# 5V_Power_Supply.net
KiCad netlist of a schematic drawn in Altium Designer
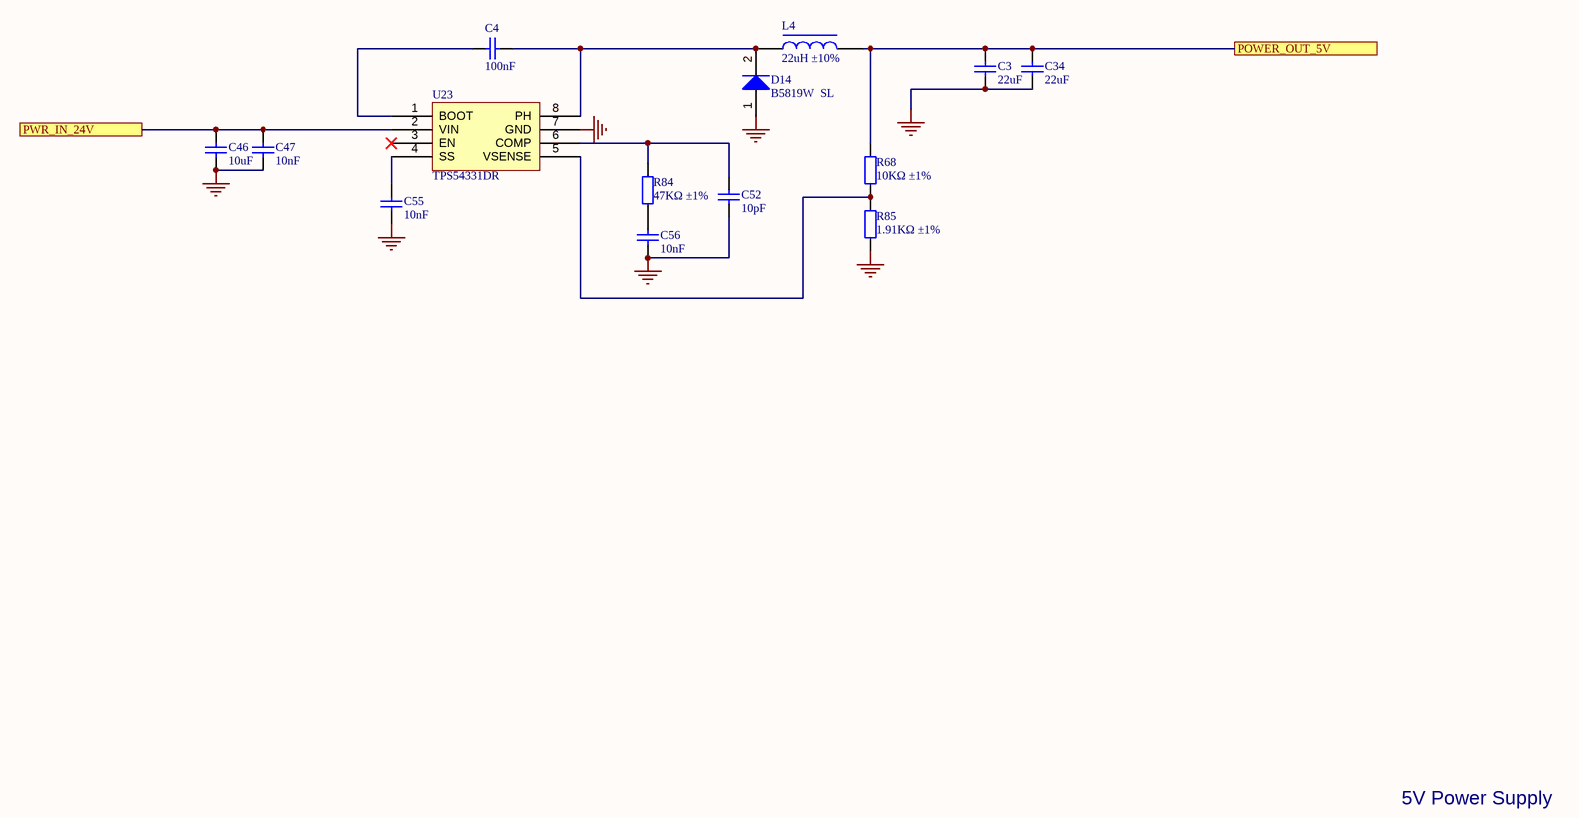
[diagram p0: 5V_Power_Supply.SchDoc]

(export (version "E")
  (design (tool "Eeschema 10.0.6"))
  (components
    (comp (ref "C3")
      (value "22uF")
      (footprint "0805_C")
      (description "Chip capacitors")
      (fields
        (field (name "MANUFACTURER") "Samsung Electro-Mechanics")
        (field (name "PARTNUMBER") "CL21A226MAQNNNE")
      )
      (libsource (lib "Cap") (part "0805 22uF (226) 20% 25V"))
    )
    (comp (ref "C4")
      (value "100nF")
      (footprint "0402_C")
      (description "Chip capacitors")
      (fields
        (field (name "MANUFACTURER") "Samsung Electro-Mechanics")
        (field (name "PARTNUMBER") "CL05B104KO5NNNC")
      )
      (libsource (lib "Cap") (part "0402 100nF (104) 10% 16V"))
    )
    (comp (ref "C34")
      (value "22uF")
      (footprint "0805_C")
      (description "Chip capacitors")
      (fields
        (field (name "MANUFACTURER") "Samsung Electro-Mechanics")
        (field (name "PARTNUMBER") "CL21A226MAQNNNE")
      )
      (libsource (lib "Cap") (part "0805 22uF (226) 20% 25V"))
    )
    (comp (ref "C46")
      (value "10uF")
      (footprint "1206_C")
      (description "Chip capacitors")
      (fields
        (field (name "MANUFACTURER") "Samsung Electro-Mechanics")
        (field (name "PARTNUMBER") "CL31A106KBHNNNE")
      )
      (libsource (lib "Cap") (part "1206 10uF (106) 10% 50V"))
    )
    (comp (ref "C47")
      (value "10nF")
      (footprint "0402_C")
      (description "Chip capacitors")
      (fields
        (field (name "MANUFACTURER") "Samsung Electro-Mechanics")
        (field (name "PARTNUMBER") "CL05B103KB5NNNC")
      )
      (libsource (lib "Cap") (part "0402 10nF (103) 10% 50V"))
    )
    (comp (ref "C52")
      (value "10pF")
      (footprint "0402_C")
      (description "Chip capacitors")
      (fields
        (field (name "MANUFACTURER") "Samsung Electro-Mechanics")
        (field (name "PARTNUMBER") "CL05C100JB5NNNC")
      )
      (libsource (lib "Cap") (part "0402 10pF (100) 5% 50V"))
    )
    (comp (ref "C55")
      (value "10nF")
      (footprint "0402_C")
      (description "Chip capacitors")
      (fields
        (field (name "MANUFACTURER") "Samsung Electro-Mechanics")
        (field (name "PARTNUMBER") "CL05B103KB5NNNC")
      )
      (libsource (lib "Cap") (part "0402 10nF (103) 10% 50V"))
    )
    (comp (ref "C56")
      (value "10nF")
      (footprint "0402_C")
      (description "Chip capacitors")
      (fields
        (field (name "MANUFACTURER") "Samsung Electro-Mechanics")
        (field (name "PARTNUMBER") "CL05B103KB5NNNC")
      )
      (libsource (lib "Cap") (part "0402 10nF (103) 10% 50V"))
    )
    (comp (ref "D14")
      (value "B5819W  SL")
      (footprint "SOD-123")
      (description "Schottky Diode")
      (libsource (lib "Diode") (part "SOD-123 B5819W  SL"))
    )
    (comp (ref "L4")
      (value "22uH ±10%")
      (footprint "INDP4040X30N")
      (description "1A 22uH ±20% SMD,4x4x3mm Power Inductors ROHS")
      (libsource (lib "IUD") (part "4x4x3 22uH 20%"))
    )
    (comp (ref "R68")
      (value "10KΩ ±1%")
      (footprint "0603_R")
      (description "Chip resistor")
      (fields (field (name "MANUFACTURER") "Uniroyal Elec") (field (name "PARTNUMBER") "0603WAF1002T5E"))
      (libsource (lib "RES") (part "0603 10K (1002) 1%"))
    )
    (comp (ref "R84")
      (value "47KΩ ±1%")
      (footprint "0402_R")
      (description "Chip resistor")
      (fields (field (name "MANUFACTURER") "Uniroyal Elec") (field (name "PARTNUMBER") "0402WGF4702TCE"))
      (libsource (lib "RES") (part "0402 47K (4702) 1%"))
    )
    (comp (ref "R85")
      (value "1.91KΩ ±1%")
      (footprint "0603_R")
      (description "Chip resistor")
      (fields (field (name "MANUFACTURER") "Uniroyal Elec") (field (name "PARTNUMBER") "0603WAF1911T5E"))
      (libsource (lib "RES") (part "0603 2K (2001) 1%"))
    )
    (comp (ref "U23")
      (value "TPS54331DR")
      (footprint "Miscellaneous Devices LC:SOIC-8_150mil")
      (description "Switching Voltage Regulators 3A 28V In Step Down SWIFT DC/DC Cnvrtr")
      (libsource (lib "PrintNC_GRBLHAL_Breakout") (part "TPS54331DR_[C9865]"))
    )
  )
  (nets
    (net (code "1") (name "/POWER_OUT_5V") (class "Default")
      (node (ref "C3") (pin "2") (pinfunction "2_2") (pintype "passive"))
      (node (ref "C34") (pin "2") (pinfunction "2_2") (pintype "passive"))
      (node (ref "L4") (pin "2") (pinfunction "2_2") (pintype "passive"))
      (node (ref "R68") (pin "2") (pinfunction "2_2") (pintype "passive"))
    )
    (net (code "2") (name "/PWR_IN_24V") (class "Default")
      (node (ref "C46") (pin "2") (pinfunction "2_2") (pintype "passive"))
      (node (ref "C47") (pin "2") (pinfunction "2_2") (pintype "passive"))
      (node (ref "U23") (pin "2") (pinfunction "VIN_2") (pintype "passive"))
    )
    (net (code "3") (name "GND") (class "Default")
      (node (ref "C3") (pin "1") (pinfunction "1_1") (pintype "passive"))
      (node (ref "C34") (pin "1") (pinfunction "1_1") (pintype "passive"))
      (node (ref "C46") (pin "1") (pinfunction "1_1") (pintype "passive"))
      (node (ref "C47") (pin "1") (pinfunction "1_1") (pintype "passive"))
      (node (ref "C52") (pin "1") (pinfunction "1_1") (pintype "passive"))
      (node (ref "C55") (pin "1") (pinfunction "1_1") (pintype "passive"))
      (node (ref "C56") (pin "1") (pinfunction "1_1") (pintype "passive"))
      (node (ref "D14") (pin "1") (pinfunction "A_1") (pintype "passive"))
      (node (ref "R85") (pin "1") (pinfunction "1_1") (pintype "passive"))
      (node (ref "U23") (pin "7") (pinfunction "GND_7") (pintype "passive"))
    )
    (net (code "4") (name "Net-(C56-Pad2)") (class "Default")
      (node (ref "C56") (pin "2") (pinfunction "2_2") (pintype "passive"))
      (node (ref "R84") (pin "1") (pinfunction "1_1") (pintype "passive"))
    )
    (net (code "5") (name "Net-(D14-K)") (class "Default")
      (node (ref "C4") (pin "2") (pinfunction "2_2") (pintype "passive"))
      (node (ref "D14") (pin "2") (pinfunction "K_2") (pintype "passive"))
      (node (ref "L4") (pin "1") (pinfunction "1_1") (pintype "passive"))
      (node (ref "U23") (pin "8") (pinfunction "PH_8") (pintype "passive"))
    )
    (net (code "6") (name "Net-(U23-BOOT)") (class "Default")
      (node (ref "C4") (pin "1") (pinfunction "1_1") (pintype "passive"))
      (node (ref "U23") (pin "1") (pinfunction "BOOT_1") (pintype "passive"))
    )
    (net (code "7") (name "Net-(U23-COMP)") (class "Default")
      (node (ref "C52") (pin "2") (pinfunction "2_2") (pintype "passive"))
      (node (ref "R84") (pin "2") (pinfunction "2_2") (pintype "passive"))
      (node (ref "U23") (pin "6") (pinfunction "COMP_6") (pintype "passive"))
    )
    (net (code "8") (name "Net-(U23-SS)") (class "Default")
      (node (ref "C55") (pin "2") (pinfunction "2_2") (pintype "passive"))
      (node (ref "U23") (pin "4") (pinfunction "SS_4") (pintype "passive"))
    )
    (net (code "9") (name "Net-(U23-VSENSE)") (class "Default")
      (node (ref "R68") (pin "1") (pinfunction "1_1") (pintype "passive"))
      (node (ref "R85") (pin "2") (pinfunction "2_2") (pintype "passive"))
      (node (ref "U23") (pin "5") (pinfunction "VSENSE_5") (pintype "passive"))
    )
    (net (code "10") (name "unconnected-(U23-EN-Pad3)") (class "Default")
      (node (ref "U23") (pin "3") (pinfunction "EN_3") (pintype "passive+no_connect"))
    )
  )
)
